# gate_delay_v2_ctrl.net
KiCad netlist of a schematic drawn in EAGLE
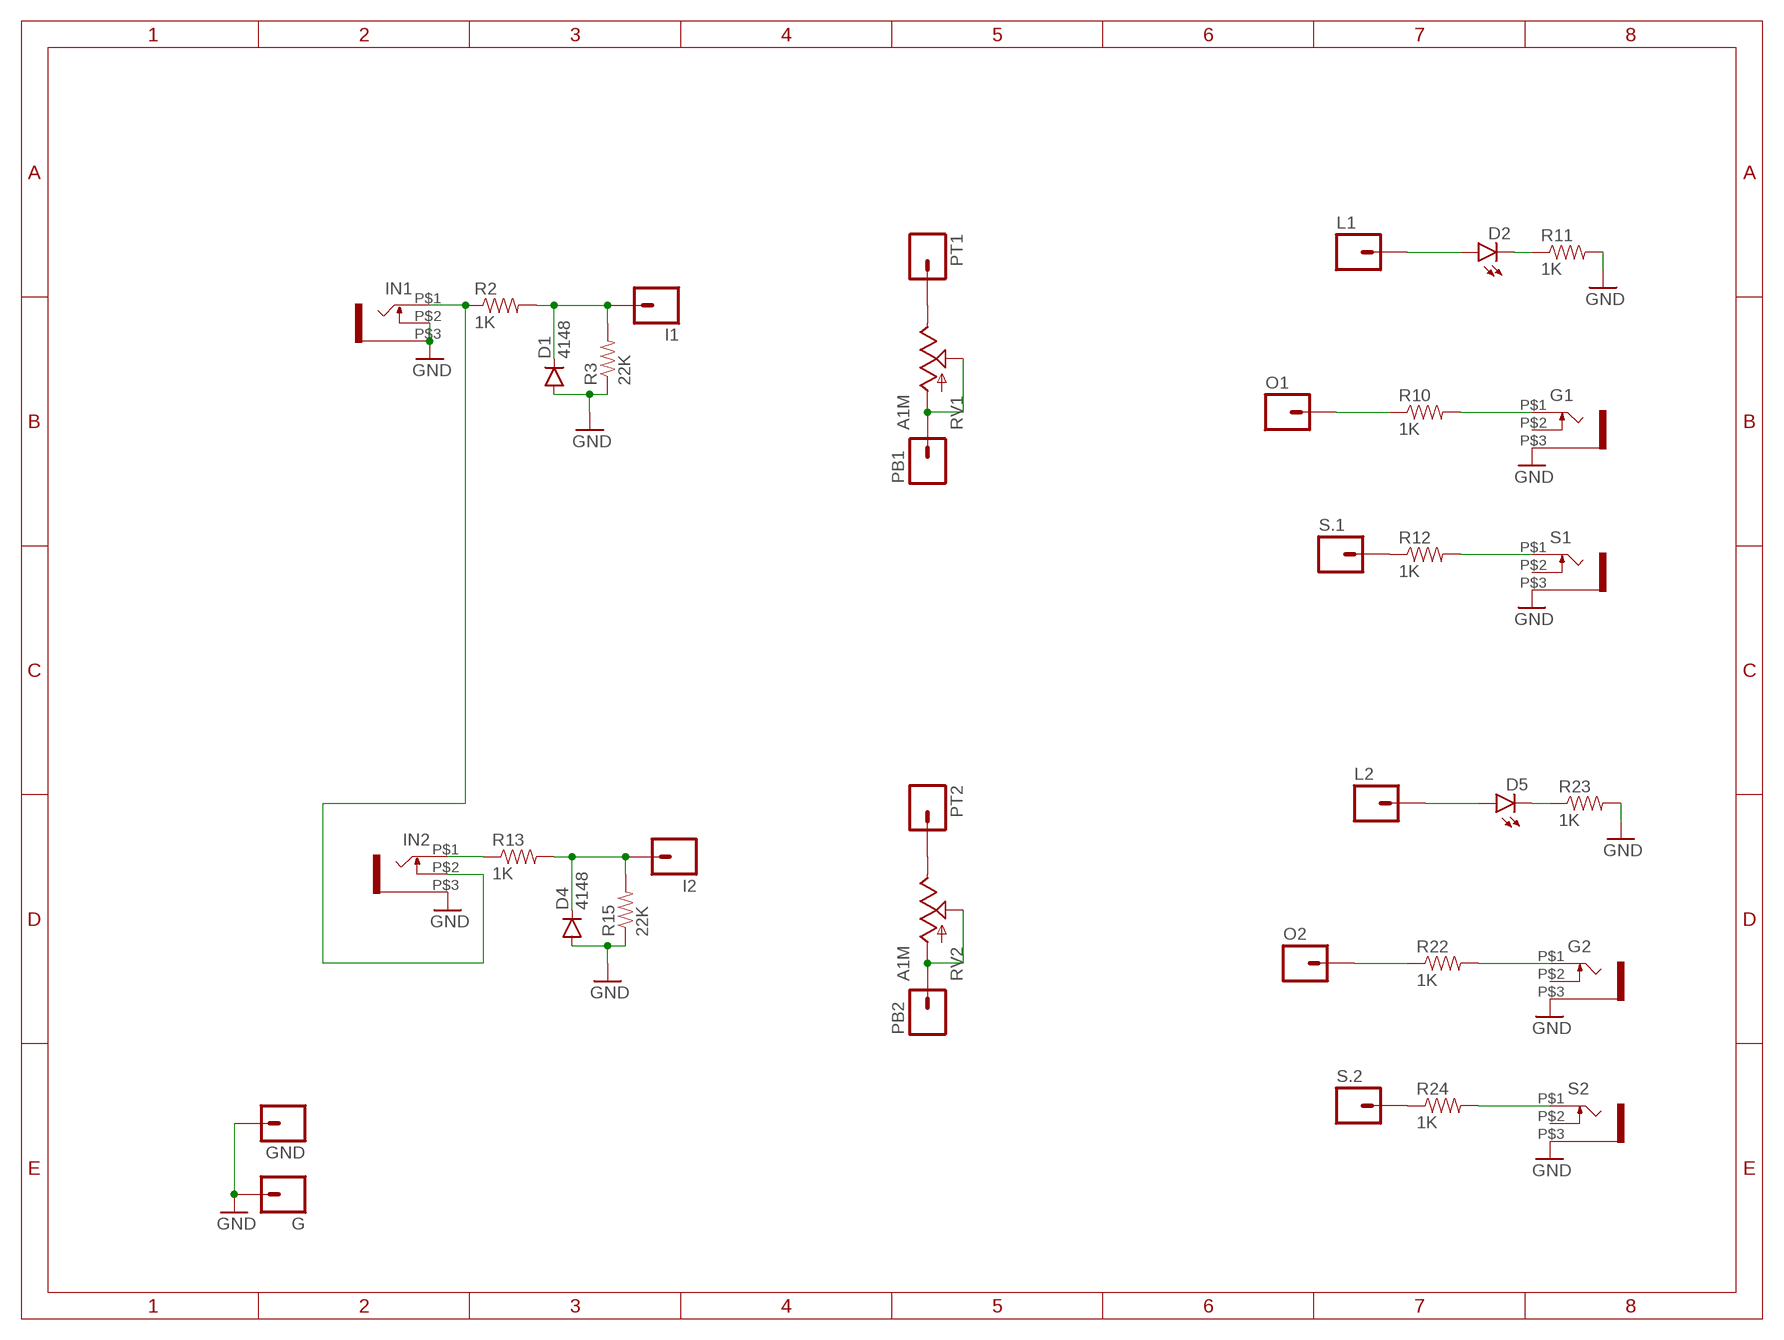
[diagram p0: schematic, sheet 1]

(export (version "E")
  (design (tool "Eeschema 10.0.6"))
  (components
    (comp (ref "D1")
      (value "4148")
      (footprint "eagle-import:SOD-123")
      (libsource (lib "eagle-import") (part "DIODESOD123"))
    )
    (comp (ref "D2")
      (value "LED3MM")
      (footprint "eagle-import:LED3MM")
      (libsource (lib "eagle-import") (part "LED3MM"))
    )
    (comp (ref "D4")
      (value "4148")
      (footprint "eagle-import:SOD-123")
      (libsource (lib "eagle-import") (part "DIODESOD123"))
    )
    (comp (ref "D5")
      (value "LED3MM")
      (footprint "eagle-import:LED3MM")
      (libsource (lib "eagle-import") (part "LED3MM"))
    )
    (comp (ref "G")
      (value "M01PTH")
      (footprint "eagle-import:1X01")
      (libsource (lib "eagle-import") (part "M01PTH"))
    )
    (comp (ref "G1")
      (value "WQP-PJ301M-12_JACK")
      (footprint "eagle-import:WQP-PJ301M-12_JACK")
      (libsource (lib "eagle-import") (part "WQP-PJ301M-12_JACK"))
    )
    (comp (ref "G2")
      (value "WQP-PJ301M-12_JACK")
      (footprint "eagle-import:WQP-PJ301M-12_JACK")
      (libsource (lib "eagle-import") (part "WQP-PJ301M-12_JACK"))
    )
    (comp (ref "GND")
      (value "M01PTH")
      (footprint "eagle-import:1X01")
      (libsource (lib "eagle-import") (part "M01PTH"))
    )
    (comp (ref "I1")
      (value "M01PTH")
      (footprint "eagle-import:1X01")
      (libsource (lib "eagle-import") (part "M01PTH"))
    )
    (comp (ref "I2")
      (value "M01PTH")
      (footprint "eagle-import:1X01")
      (libsource (lib "eagle-import") (part "M01PTH"))
    )
    (comp (ref "IN1")
      (value "WQP-PJ301M-12_JACK")
      (footprint "eagle-import:WQP-PJ301M-12_JACK")
      (libsource (lib "eagle-import") (part "WQP-PJ301M-12_JACK"))
    )
    (comp (ref "IN2")
      (value "WQP-PJ301M-12_JACK")
      (footprint "eagle-import:WQP-PJ301M-12_JACK")
      (libsource (lib "eagle-import") (part "WQP-PJ301M-12_JACK"))
    )
    (comp (ref "L1")
      (value "M01PTH")
      (footprint "eagle-import:1X01")
      (libsource (lib "eagle-import") (part "M01PTH"))
    )
    (comp (ref "L2")
      (value "M01PTH")
      (footprint "eagle-import:1X01")
      (libsource (lib "eagle-import") (part "M01PTH"))
    )
    (comp (ref "O1")
      (value "M01PTH")
      (footprint "eagle-import:1X01")
      (libsource (lib "eagle-import") (part "M01PTH"))
    )
    (comp (ref "O2")
      (value "M01PTH")
      (footprint "eagle-import:1X01")
      (libsource (lib "eagle-import") (part "M01PTH"))
    )
    (comp (ref "PB1")
      (value "M01PTH")
      (footprint "eagle-import:1X01")
      (libsource (lib "eagle-import") (part "M01PTH"))
    )
    (comp (ref "PB2")
      (value "M01PTH")
      (footprint "eagle-import:1X01")
      (libsource (lib "eagle-import") (part "M01PTH"))
    )
    (comp (ref "PT1")
      (value "M01PTH")
      (footprint "eagle-import:1X01")
      (libsource (lib "eagle-import") (part "M01PTH"))
    )
    (comp (ref "PT2")
      (value "M01PTH")
      (footprint "eagle-import:1X01")
      (libsource (lib "eagle-import") (part "M01PTH"))
    )
    (comp (ref "R2")
      (value "1K")
      (footprint "eagle-import:0805@1")
      (libsource (lib "eagle-import") (part "RESISTOR0805-RES"))
    )
    (comp (ref "R3")
      (value "22K")
      (footprint "eagle-import:0805@1")
      (libsource (lib "eagle-import") (part "RESISTOR0805-RES"))
    )
    (comp (ref "R10")
      (value "1K")
      (footprint "eagle-import:0805@1")
      (libsource (lib "eagle-import") (part "RESISTOR0805-RES"))
    )
    (comp (ref "R11")
      (value "1K")
      (footprint "eagle-import:0805@1")
      (libsource (lib "eagle-import") (part "RESISTOR0805-RES"))
    )
    (comp (ref "R12")
      (value "1K")
      (footprint "eagle-import:0805@1")
      (libsource (lib "eagle-import") (part "RESISTOR0805-RES"))
    )
    (comp (ref "R13")
      (value "1K")
      (footprint "eagle-import:0805@1")
      (libsource (lib "eagle-import") (part "RESISTOR0805-RES"))
    )
    (comp (ref "R15")
      (value "22K")
      (footprint "eagle-import:0805@1")
      (libsource (lib "eagle-import") (part "RESISTOR0805-RES"))
    )
    (comp (ref "R22")
      (value "1K")
      (footprint "eagle-import:0805@1")
      (libsource (lib "eagle-import") (part "RESISTOR0805-RES"))
    )
    (comp (ref "R23")
      (value "1K")
      (footprint "eagle-import:0805@1")
      (libsource (lib "eagle-import") (part "RESISTOR0805-RES"))
    )
    (comp (ref "R24")
      (value "1K")
      (footprint "eagle-import:0805@1")
      (libsource (lib "eagle-import") (part "RESISTOR0805-RES"))
    )
    (comp (ref "RV1")
      (value "A1M")
      (footprint "eagle-import:ALPS_POT")
      (libsource (lib "eagle-import") (part "POT"))
    )
    (comp (ref "RV2")
      (value "A1M")
      (footprint "eagle-import:ALPS_POT")
      (libsource (lib "eagle-import") (part "POT"))
    )
    (comp (ref "S.1")
      (value "M01PTH")
      (footprint "eagle-import:1X01")
      (libsource (lib "eagle-import") (part "M01PTH"))
    )
    (comp (ref "S.2")
      (value "M01PTH")
      (footprint "eagle-import:1X01")
      (libsource (lib "eagle-import") (part "M01PTH"))
    )
    (comp (ref "S1")
      (value "WQP-PJ301M-12_JACK")
      (footprint "eagle-import:WQP-PJ301M-12_JACK")
      (libsource (lib "eagle-import") (part "WQP-PJ301M-12_JACK"))
    )
    (comp (ref "S2")
      (value "WQP-PJ301M-12_JACK")
      (footprint "eagle-import:WQP-PJ301M-12_JACK")
      (libsource (lib "eagle-import") (part "WQP-PJ301M-12_JACK"))
    )
  )
  (nets
    (net (code "1") (name "GND") (class "Default")
      (node (ref "D1") (pin "A") (pinfunction "A_A") (pintype "passive"))
      (node (ref "D4") (pin "A") (pinfunction "A_A") (pintype "passive"))
      (node (ref "G") (pin "1") (pinfunction "1_1") (pintype "passive"))
      (node (ref "G1") (pin "P$3") (pinfunction "1_P$3") (pintype "passive"))
      (node (ref "G2") (pin "P$3") (pinfunction "1_P$3") (pintype "passive"))
      (node (ref "GND") (pin "1") (pinfunction "1_1") (pintype "passive"))
      (node (ref "IN1") (pin "P$2") (pinfunction "3_P$2") (pintype "passive"))
      (node (ref "IN1") (pin "P$3") (pinfunction "1_P$3") (pintype "passive"))
      (node (ref "IN2") (pin "P$3") (pinfunction "1_P$3") (pintype "passive"))
      (node (ref "R11") (pin "2") (pinfunction "2_2") (pintype "passive"))
      (node (ref "R15") (pin "1") (pinfunction "1_1") (pintype "passive"))
      (node (ref "R23") (pin "2") (pinfunction "2_2") (pintype "passive"))
      (node (ref "R3") (pin "1") (pinfunction "1_1") (pintype "passive"))
      (node (ref "S1") (pin "P$3") (pinfunction "1_P$3") (pintype "passive"))
      (node (ref "S2") (pin "P$3") (pinfunction "1_P$3") (pintype "passive"))
    )
    (net (code "2") (name "Net-(D1-PadC)") (class "Default")
      (node (ref "D1") (pin "C") (pinfunction "C_C") (pintype "passive"))
      (node (ref "I1") (pin "1") (pinfunction "1_1") (pintype "passive"))
      (node (ref "R2") (pin "2") (pinfunction "2_2") (pintype "passive"))
      (node (ref "R3") (pin "2") (pinfunction "2_2") (pintype "passive"))
    )
    (net (code "3") (name "Net-(D2-C)") (class "Default")
      (node (ref "D2") (pin "K") (pinfunction "C_K") (pintype "passive"))
      (node (ref "R11") (pin "1") (pinfunction "1_1") (pintype "passive"))
    )
    (net (code "4") (name "Net-(D2-PadA)") (class "Default")
      (node (ref "D2") (pin "A") (pinfunction "A_A") (pintype "passive"))
      (node (ref "L1") (pin "1") (pinfunction "1_1") (pintype "passive"))
    )
    (net (code "5") (name "Net-(D4-PadC)") (class "Default")
      (node (ref "D4") (pin "C") (pinfunction "C_C") (pintype "passive"))
      (node (ref "I2") (pin "1") (pinfunction "1_1") (pintype "passive"))
      (node (ref "R13") (pin "2") (pinfunction "2_2") (pintype "passive"))
      (node (ref "R15") (pin "2") (pinfunction "2_2") (pintype "passive"))
    )
    (net (code "6") (name "Net-(D5-C)") (class "Default")
      (node (ref "D5") (pin "K") (pinfunction "C_K") (pintype "passive"))
      (node (ref "R23") (pin "1") (pinfunction "1_1") (pintype "passive"))
    )
    (net (code "7") (name "Net-(D5-PadA)") (class "Default")
      (node (ref "D5") (pin "A") (pinfunction "A_A") (pintype "passive"))
      (node (ref "L2") (pin "1") (pinfunction "1_1") (pintype "passive"))
    )
    (net (code "8") (name "Net-(G1-2)") (class "Default")
      (node (ref "G1") (pin "P$1") (pinfunction "2_P$1") (pintype "passive"))
      (node (ref "R10") (pin "2") (pinfunction "2_2") (pintype "passive"))
    )
    (net (code "9") (name "Net-(G2-2)") (class "Default")
      (node (ref "G2") (pin "P$1") (pinfunction "2_P$1") (pintype "passive"))
      (node (ref "R22") (pin "2") (pinfunction "2_2") (pintype "passive"))
    )
    (net (code "10") (name "Net-(IN1-2)") (class "Default")
      (node (ref "IN1") (pin "P$1") (pinfunction "2_P$1") (pintype "passive"))
      (node (ref "IN2") (pin "P$2") (pinfunction "3_P$2") (pintype "passive"))
      (node (ref "R2") (pin "1") (pinfunction "1_1") (pintype "passive"))
    )
    (net (code "11") (name "Net-(IN2-2)") (class "Default")
      (node (ref "IN2") (pin "P$1") (pinfunction "2_P$1") (pintype "passive"))
      (node (ref "R13") (pin "1") (pinfunction "1_1") (pintype "passive"))
    )
    (net (code "12") (name "Net-(O1-Pad1)") (class "Default")
      (node (ref "O1") (pin "1") (pinfunction "1_1") (pintype "passive"))
      (node (ref "R10") (pin "1") (pinfunction "1_1") (pintype "passive"))
    )
    (net (code "13") (name "Net-(O2-Pad1)") (class "Default")
      (node (ref "O2") (pin "1") (pinfunction "1_1") (pintype "passive"))
      (node (ref "R22") (pin "1") (pinfunction "1_1") (pintype "passive"))
    )
    (net (code "14") (name "Net-(R12-Pad1)") (class "Default")
      (node (ref "R12") (pin "1") (pinfunction "1_1") (pintype "passive"))
      (node (ref "S.1") (pin "1") (pinfunction "1_1") (pintype "passive"))
    )
    (net (code "15") (name "Net-(R24-Pad1)") (class "Default")
      (node (ref "R24") (pin "1") (pinfunction "1_1") (pintype "passive"))
      (node (ref "S.2") (pin "1") (pinfunction "1_1") (pintype "passive"))
    )
    (net (code "16") (name "Net-(RV1-A)") (class "Default")
      (node (ref "PB1") (pin "1") (pinfunction "1_1") (pintype "passive"))
      (node (ref "RV1") (pin "P$2") (pinfunction "S_P$2") (pintype "passive"))
      (node (ref "RV1") (pin "P$3") (pinfunction "A_P$3") (pintype "passive"))
    )
    (net (code "17") (name "Net-(RV1-E)") (class "Default")
      (node (ref "PT1") (pin "1") (pinfunction "1_1") (pintype "passive"))
      (node (ref "RV1") (pin "P$1") (pinfunction "E_P$1") (pintype "passive"))
    )
    (net (code "18") (name "Net-(RV2-A)") (class "Default")
      (node (ref "PB2") (pin "1") (pinfunction "1_1") (pintype "passive"))
      (node (ref "RV2") (pin "P$2") (pinfunction "S_P$2") (pintype "passive"))
      (node (ref "RV2") (pin "P$3") (pinfunction "A_P$3") (pintype "passive"))
    )
    (net (code "19") (name "Net-(RV2-E)") (class "Default")
      (node (ref "PT2") (pin "1") (pinfunction "1_1") (pintype "passive"))
      (node (ref "RV2") (pin "P$1") (pinfunction "E_P$1") (pintype "passive"))
    )
    (net (code "20") (name "Net-(S1-2)") (class "Default")
      (node (ref "R12") (pin "2") (pinfunction "2_2") (pintype "passive"))
      (node (ref "S1") (pin "P$1") (pinfunction "2_P$1") (pintype "passive"))
    )
    (net (code "21") (name "Net-(S2-2)") (class "Default")
      (node (ref "R24") (pin "2") (pinfunction "2_2") (pintype "passive"))
      (node (ref "S2") (pin "P$1") (pinfunction "2_P$1") (pintype "passive"))
    )
    (net (code "22") (name "unconnected-(G1-3-PadP$2)") (class "Default")
      (node (ref "G1") (pin "P$2") (pinfunction "3_P$2") (pintype "passive"))
    )
    (net (code "23") (name "unconnected-(G2-3-PadP$2)") (class "Default")
      (node (ref "G2") (pin "P$2") (pinfunction "3_P$2") (pintype "passive"))
    )
    (net (code "24") (name "unconnected-(S1-3-PadP$2)") (class "Default")
      (node (ref "S1") (pin "P$2") (pinfunction "3_P$2") (pintype "passive"))
    )
    (net (code "25") (name "unconnected-(S2-3-PadP$2)") (class "Default")
      (node (ref "S2") (pin "P$2") (pinfunction "3_P$2") (pintype "passive"))
    )
  )
)
